# decoder.net
KiCad netlist of a schematic drawn in EAGLE
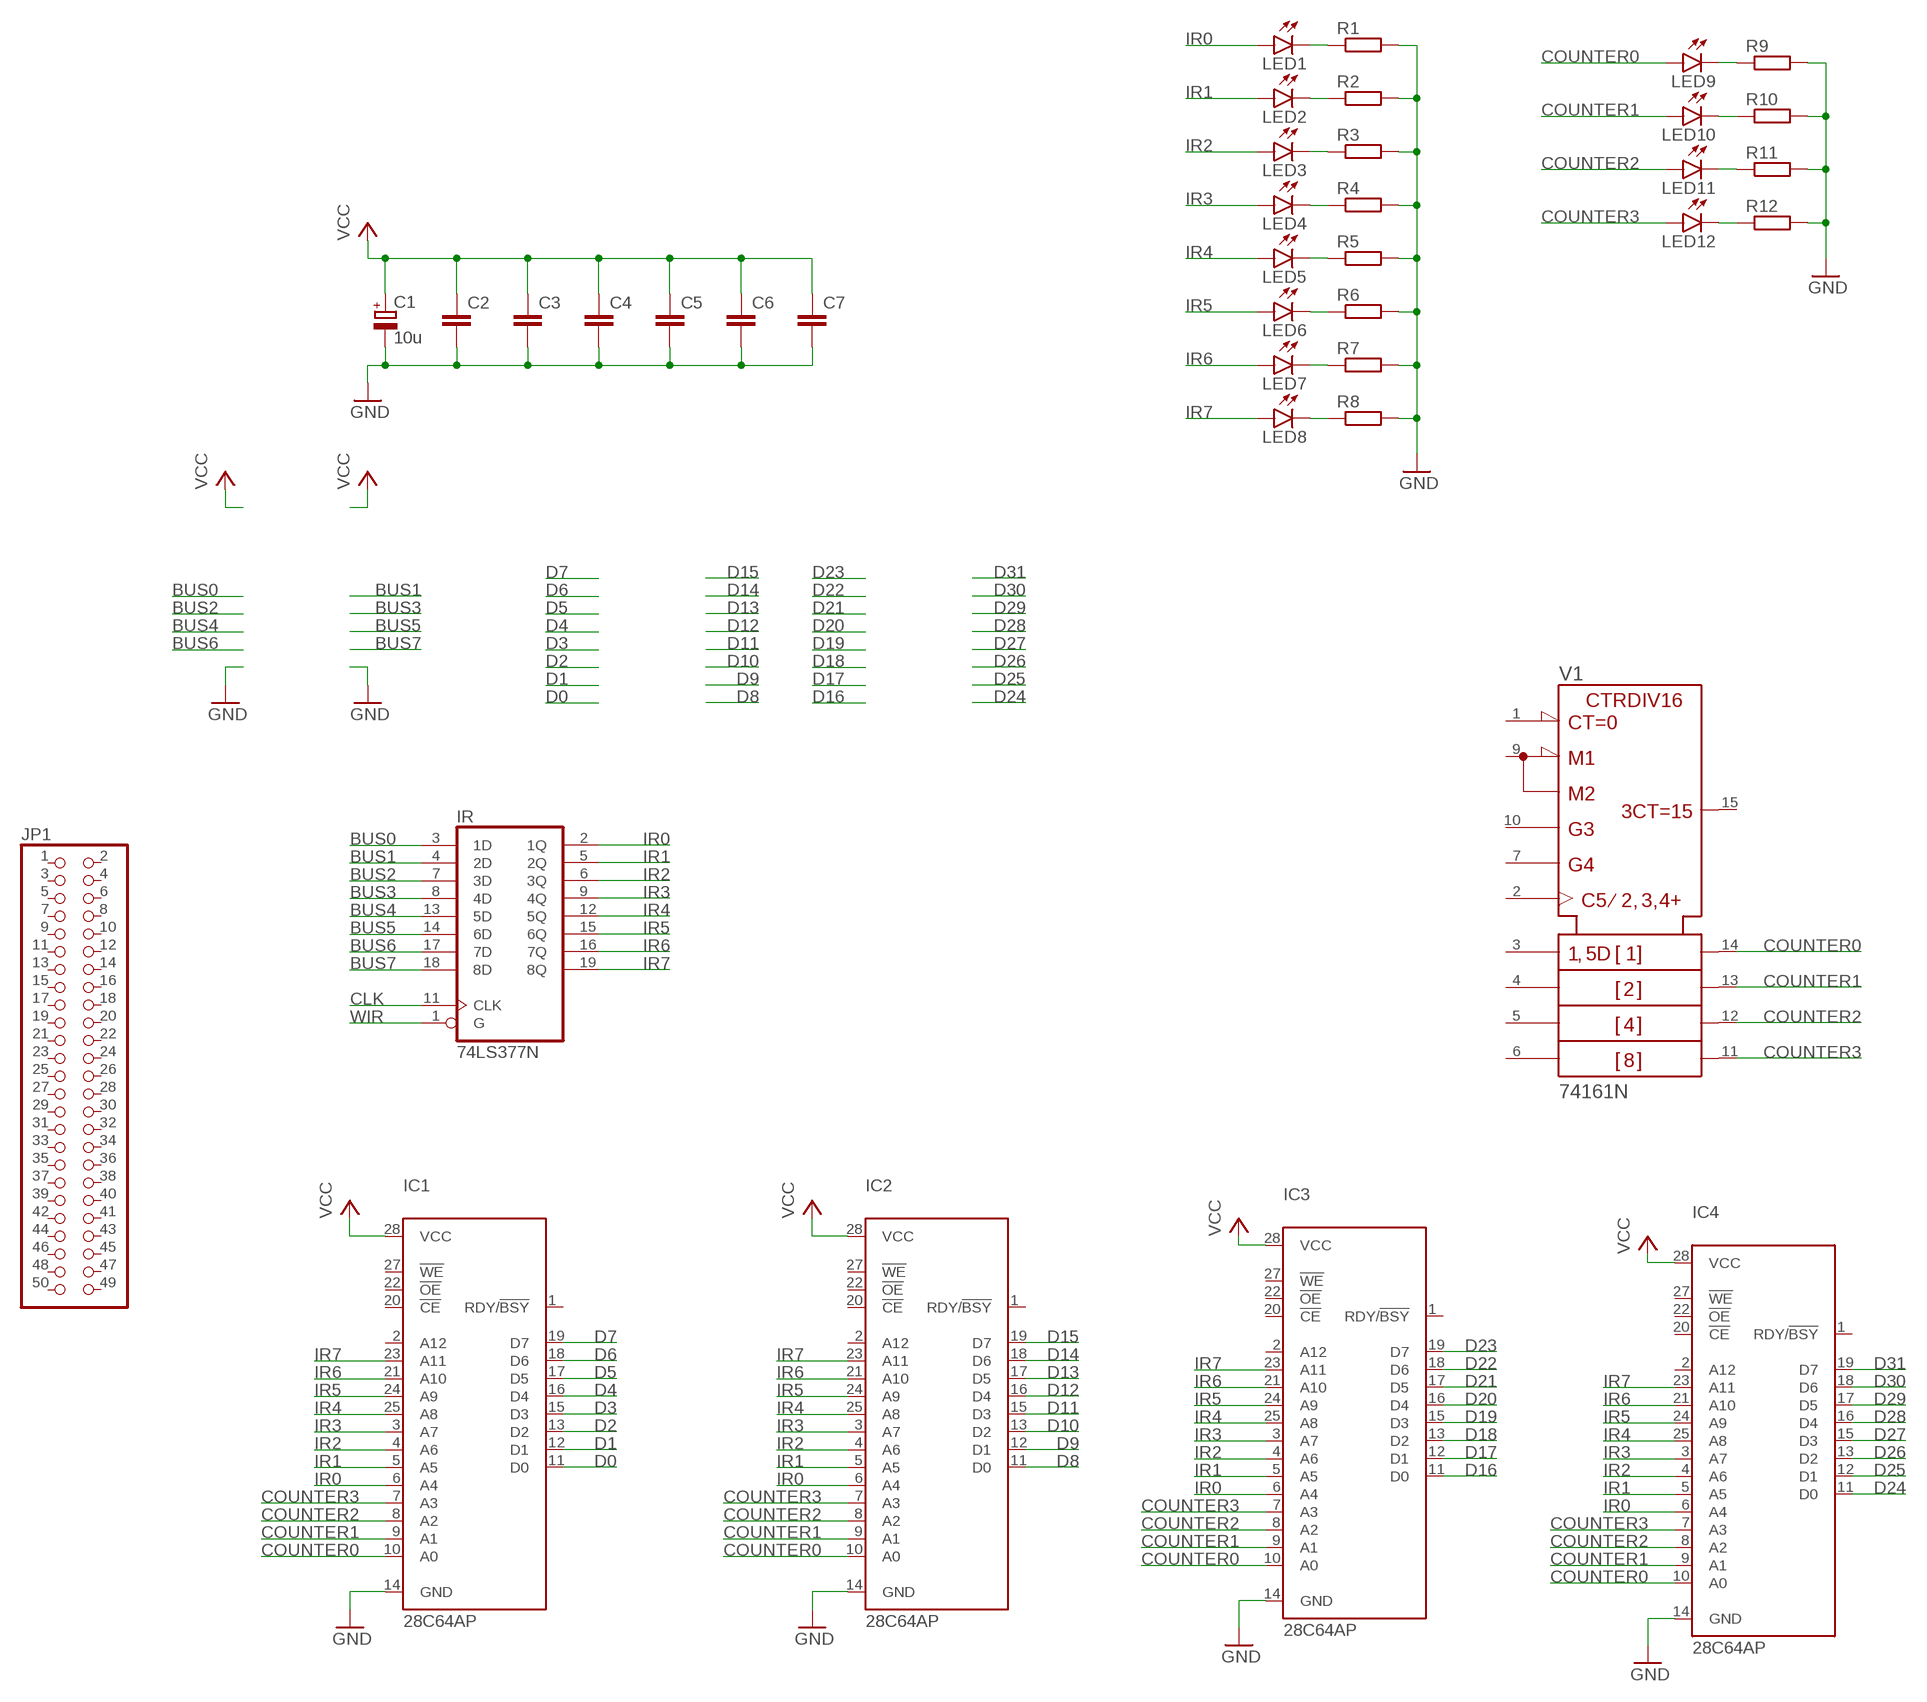
[diagram p0: schematic, sheet 1]

(export (version "E")
  (design (tool "Eeschema 10.0.6"))
  (components
    (comp (ref "C1")
      (value "10u")
      (footprint "eagle-import:E5-8,5")
      (libsource (lib "eagle-import") (part "CPOL-EUE5-8.5"))
    )
    (comp (ref "C2")
      (value "C-EU025-024X044")
      (footprint "eagle-import:C025-024X044")
      (libsource (lib "eagle-import") (part "C-EU025-024X044"))
    )
    (comp (ref "C3")
      (value "C-EU025-024X044")
      (footprint "eagle-import:C025-024X044")
      (libsource (lib "eagle-import") (part "C-EU025-024X044"))
    )
    (comp (ref "C4")
      (value "C-EU025-024X044")
      (footprint "eagle-import:C025-024X044")
      (libsource (lib "eagle-import") (part "C-EU025-024X044"))
    )
    (comp (ref "C5")
      (value "C-EU025-024X044")
      (footprint "eagle-import:C025-024X044")
      (libsource (lib "eagle-import") (part "C-EU025-024X044"))
    )
    (comp (ref "C6")
      (value "C-EU025-024X044")
      (footprint "eagle-import:C025-024X044")
      (libsource (lib "eagle-import") (part "C-EU025-024X044"))
    )
    (comp (ref "C7")
      (value "C-EU025-024X044")
      (footprint "eagle-import:C025-024X044")
      (libsource (lib "eagle-import") (part "C-EU025-024X044"))
    )
    (comp (ref "IC1")
      (value "28C64AP")
      (footprint "eagle-import:DIL28-6")
      (fields (field (name "MPN") "AT28C64B-15PU"))
      (libsource (lib "eagle-import") (part "2864APC"))
    )
    (comp (ref "IC2")
      (value "28C64AP")
      (footprint "eagle-import:DIL28-6")
      (fields (field (name "MPN") "AT28C64B-15PU"))
      (libsource (lib "eagle-import") (part "2864APC"))
    )
    (comp (ref "IC3")
      (value "28C64AP")
      (footprint "eagle-import:DIL28-6")
      (fields (field (name "MPN") "AT28C64B-15PU"))
      (libsource (lib "eagle-import") (part "2864APC"))
    )
    (comp (ref "IC4")
      (value "28C64AP")
      (footprint "eagle-import:DIL28-6")
      (fields (field (name "MPN") "AT28C64B-15PU"))
      (libsource (lib "eagle-import") (part "2864APC"))
    )
    (comp (ref "IR")
      (value "74LS377N")
      (footprint "eagle-import:DIL20")
      (libsource (lib "eagle-import") (part "74377NLS"))
    )
    (comp (ref "JP1")
      (value "PINHD-2X25/90")
      (footprint "eagle-import:2X25_90")
      (libsource (lib "eagle-import") (part "PINHD-2X25/90"))
    )
    (comp (ref "LED1")
      (value "LEDSML1206")
      (footprint "eagle-import:SML1206")
      (libsource (lib "eagle-import") (part "LEDSML1206"))
    )
    (comp (ref "LED2")
      (value "LEDSML1206")
      (footprint "eagle-import:SML1206")
      (libsource (lib "eagle-import") (part "LEDSML1206"))
    )
    (comp (ref "LED3")
      (value "LEDSML1206")
      (footprint "eagle-import:SML1206")
      (libsource (lib "eagle-import") (part "LEDSML1206"))
    )
    (comp (ref "LED4")
      (value "LEDSML1206")
      (footprint "eagle-import:SML1206")
      (libsource (lib "eagle-import") (part "LEDSML1206"))
    )
    (comp (ref "LED5")
      (value "LEDSML1206")
      (footprint "eagle-import:SML1206")
      (libsource (lib "eagle-import") (part "LEDSML1206"))
    )
    (comp (ref "LED6")
      (value "LEDSML1206")
      (footprint "eagle-import:SML1206")
      (libsource (lib "eagle-import") (part "LEDSML1206"))
    )
    (comp (ref "LED7")
      (value "LEDSML1206")
      (footprint "eagle-import:SML1206")
      (libsource (lib "eagle-import") (part "LEDSML1206"))
    )
    (comp (ref "LED8")
      (value "LEDSML1206")
      (footprint "eagle-import:SML1206")
      (libsource (lib "eagle-import") (part "LEDSML1206"))
    )
    (comp (ref "LED9")
      (value "LEDSML1206")
      (footprint "eagle-import:SML1206")
      (libsource (lib "eagle-import") (part "LEDSML1206"))
    )
    (comp (ref "LED10")
      (value "LEDSML1206")
      (footprint "eagle-import:SML1206")
      (libsource (lib "eagle-import") (part "LEDSML1206"))
    )
    (comp (ref "LED11")
      (value "LEDSML1206")
      (footprint "eagle-import:SML1206")
      (libsource (lib "eagle-import") (part "LEDSML1206"))
    )
    (comp (ref "LED12")
      (value "LEDSML1206")
      (footprint "eagle-import:SML1206")
      (libsource (lib "eagle-import") (part "LEDSML1206"))
    )
    (comp (ref "R1")
      (value "R-EU_R0805")
      (footprint "eagle-import:R0805")
      (libsource (lib "eagle-import") (part "R-EU_R0805"))
    )
    (comp (ref "R2")
      (value "R-EU_R0805")
      (footprint "eagle-import:R0805")
      (libsource (lib "eagle-import") (part "R-EU_R0805"))
    )
    (comp (ref "R3")
      (value "R-EU_R0805")
      (footprint "eagle-import:R0805")
      (libsource (lib "eagle-import") (part "R-EU_R0805"))
    )
    (comp (ref "R4")
      (value "R-EU_R0805")
      (footprint "eagle-import:R0805")
      (libsource (lib "eagle-import") (part "R-EU_R0805"))
    )
    (comp (ref "R5")
      (value "R-EU_R0805")
      (footprint "eagle-import:R0805")
      (libsource (lib "eagle-import") (part "R-EU_R0805"))
    )
    (comp (ref "R6")
      (value "R-EU_R0805")
      (footprint "eagle-import:R0805")
      (libsource (lib "eagle-import") (part "R-EU_R0805"))
    )
    (comp (ref "R7")
      (value "R-EU_R0805")
      (footprint "eagle-import:R0805")
      (libsource (lib "eagle-import") (part "R-EU_R0805"))
    )
    (comp (ref "R8")
      (value "R-EU_R0805")
      (footprint "eagle-import:R0805")
      (libsource (lib "eagle-import") (part "R-EU_R0805"))
    )
    (comp (ref "R9")
      (value "R-EU_R0805")
      (footprint "eagle-import:R0805")
      (libsource (lib "eagle-import") (part "R-EU_R0805"))
    )
    (comp (ref "R10")
      (value "R-EU_R0805")
      (footprint "eagle-import:R0805")
      (libsource (lib "eagle-import") (part "R-EU_R0805"))
    )
    (comp (ref "R11")
      (value "R-EU_R0805")
      (footprint "eagle-import:R0805")
      (libsource (lib "eagle-import") (part "R-EU_R0805"))
    )
    (comp (ref "R12")
      (value "R-EU_R0805")
      (footprint "eagle-import:R0805")
      (libsource (lib "eagle-import") (part "R-EU_R0805"))
    )
    (comp (ref "V1")
      (value "74161N")
      (footprint "eagle-import:DIL16")
      (libsource (lib "eagle-import") (part "74161N"))
    )
  )
  (nets
    (net (code "1") (name "/BUS0") (class "Default")
      (node (ref "IR") (pin "3") (pinfunction "1D_3") (pintype "input"))
    )
    (net (code "2") (name "/BUS1") (class "Default")
      (node (ref "IR") (pin "4") (pinfunction "2D_4") (pintype "input"))
    )
    (net (code "3") (name "/BUS2") (class "Default")
      (node (ref "IR") (pin "7") (pinfunction "3D_7") (pintype "input"))
    )
    (net (code "4") (name "/BUS3") (class "Default")
      (node (ref "IR") (pin "8") (pinfunction "4D_8") (pintype "input"))
    )
    (net (code "5") (name "/BUS4") (class "Default")
      (node (ref "IR") (pin "13") (pinfunction "5D_13") (pintype "input"))
    )
    (net (code "6") (name "/BUS5") (class "Default")
      (node (ref "IR") (pin "14") (pinfunction "6D_14") (pintype "input"))
    )
    (net (code "7") (name "/BUS6") (class "Default")
      (node (ref "IR") (pin "17") (pinfunction "7D_17") (pintype "input"))
    )
    (net (code "8") (name "/BUS7") (class "Default")
      (node (ref "IR") (pin "18") (pinfunction "8D_18") (pintype "input"))
    )
    (net (code "9") (name "/CLK") (class "Default")
      (node (ref "IR") (pin "11") (pinfunction "CLK_11") (pintype "input"))
    )
    (net (code "10") (name "/COUNTER0") (class "Default")
      (node (ref "IC1") (pin "10") (pinfunction "A0_10") (pintype "input"))
      (node (ref "IC2") (pin "10") (pinfunction "A0_10") (pintype "input"))
      (node (ref "IC3") (pin "10") (pinfunction "A0_10") (pintype "input"))
      (node (ref "IC4") (pin "10") (pinfunction "A0_10") (pintype "input"))
      (node (ref "LED9") (pin "A") (pinfunction "A_A") (pintype "passive"))
      (node (ref "V1") (pin "14") (pinfunction "QA_14") (pintype "output"))
    )
    (net (code "11") (name "/COUNTER1") (class "Default")
      (node (ref "IC1") (pin "9") (pinfunction "A1_9") (pintype "input"))
      (node (ref "IC2") (pin "9") (pinfunction "A1_9") (pintype "input"))
      (node (ref "IC3") (pin "9") (pinfunction "A1_9") (pintype "input"))
      (node (ref "IC4") (pin "9") (pinfunction "A1_9") (pintype "input"))
      (node (ref "LED10") (pin "A") (pinfunction "A_A") (pintype "passive"))
      (node (ref "V1") (pin "13") (pinfunction "QB_13") (pintype "output"))
    )
    (net (code "12") (name "/COUNTER2") (class "Default")
      (node (ref "IC1") (pin "8") (pinfunction "A2_8") (pintype "input"))
      (node (ref "IC2") (pin "8") (pinfunction "A2_8") (pintype "input"))
      (node (ref "IC3") (pin "8") (pinfunction "A2_8") (pintype "input"))
      (node (ref "IC4") (pin "8") (pinfunction "A2_8") (pintype "input"))
      (node (ref "LED11") (pin "A") (pinfunction "A_A") (pintype "passive"))
      (node (ref "V1") (pin "12") (pinfunction "QC_12") (pintype "output"))
    )
    (net (code "13") (name "/COUNTER3") (class "Default")
      (node (ref "IC1") (pin "7") (pinfunction "A3_7") (pintype "input"))
      (node (ref "IC2") (pin "7") (pinfunction "A3_7") (pintype "input"))
      (node (ref "IC3") (pin "7") (pinfunction "A3_7") (pintype "input"))
      (node (ref "IC4") (pin "7") (pinfunction "A3_7") (pintype "input"))
      (node (ref "LED12") (pin "A") (pinfunction "A_A") (pintype "passive"))
      (node (ref "V1") (pin "11") (pinfunction "QD_11") (pintype "output"))
    )
    (net (code "14") (name "/D0") (class "Default")
      (node (ref "IC1") (pin "11") (pinfunction "D0_11") (pintype "tri_state"))
    )
    (net (code "15") (name "/D1") (class "Default")
      (node (ref "IC1") (pin "12") (pinfunction "D1_12") (pintype "tri_state"))
    )
    (net (code "16") (name "/D2") (class "Default")
      (node (ref "IC1") (pin "13") (pinfunction "D2_13") (pintype "tri_state"))
    )
    (net (code "17") (name "/D3") (class "Default")
      (node (ref "IC1") (pin "15") (pinfunction "D3_15") (pintype "tri_state"))
    )
    (net (code "18") (name "/D4") (class "Default")
      (node (ref "IC1") (pin "16") (pinfunction "D4_16") (pintype "tri_state"))
    )
    (net (code "19") (name "/D5") (class "Default")
      (node (ref "IC1") (pin "17") (pinfunction "D5_17") (pintype "tri_state"))
    )
    (net (code "20") (name "/D6") (class "Default")
      (node (ref "IC1") (pin "18") (pinfunction "D6_18") (pintype "tri_state"))
    )
    (net (code "21") (name "/D7") (class "Default")
      (node (ref "IC1") (pin "19") (pinfunction "D7_19") (pintype "tri_state"))
    )
    (net (code "22") (name "/D8") (class "Default")
      (node (ref "IC2") (pin "11") (pinfunction "D0_11") (pintype "tri_state"))
    )
    (net (code "23") (name "/D9") (class "Default")
      (node (ref "IC2") (pin "12") (pinfunction "D1_12") (pintype "tri_state"))
    )
    (net (code "24") (name "/D10") (class "Default")
      (node (ref "IC2") (pin "13") (pinfunction "D2_13") (pintype "tri_state"))
    )
    (net (code "25") (name "/D11") (class "Default")
      (node (ref "IC2") (pin "15") (pinfunction "D3_15") (pintype "tri_state"))
    )
    (net (code "26") (name "/D12") (class "Default")
      (node (ref "IC2") (pin "16") (pinfunction "D4_16") (pintype "tri_state"))
    )
    (net (code "27") (name "/D13") (class "Default")
      (node (ref "IC2") (pin "17") (pinfunction "D5_17") (pintype "tri_state"))
    )
    (net (code "28") (name "/D14") (class "Default")
      (node (ref "IC2") (pin "18") (pinfunction "D6_18") (pintype "tri_state"))
    )
    (net (code "29") (name "/D15") (class "Default")
      (node (ref "IC2") (pin "19") (pinfunction "D7_19") (pintype "tri_state"))
    )
    (net (code "30") (name "/D16") (class "Default")
      (node (ref "IC3") (pin "11") (pinfunction "D0_11") (pintype "tri_state"))
    )
    (net (code "31") (name "/D17") (class "Default")
      (node (ref "IC3") (pin "12") (pinfunction "D1_12") (pintype "tri_state"))
    )
    (net (code "32") (name "/D18") (class "Default")
      (node (ref "IC3") (pin "13") (pinfunction "D2_13") (pintype "tri_state"))
    )
    (net (code "33") (name "/D19") (class "Default")
      (node (ref "IC3") (pin "15") (pinfunction "D3_15") (pintype "tri_state"))
    )
    (net (code "34") (name "/D20") (class "Default")
      (node (ref "IC3") (pin "16") (pinfunction "D4_16") (pintype "tri_state"))
    )
    (net (code "35") (name "/D21") (class "Default")
      (node (ref "IC3") (pin "17") (pinfunction "D5_17") (pintype "tri_state"))
    )
    (net (code "36") (name "/D22") (class "Default")
      (node (ref "IC3") (pin "18") (pinfunction "D6_18") (pintype "tri_state"))
    )
    (net (code "37") (name "/D23") (class "Default")
      (node (ref "IC3") (pin "19") (pinfunction "D7_19") (pintype "tri_state"))
    )
    (net (code "38") (name "/D24") (class "Default")
      (node (ref "IC4") (pin "11") (pinfunction "D0_11") (pintype "tri_state"))
    )
    (net (code "39") (name "/D25") (class "Default")
      (node (ref "IC4") (pin "12") (pinfunction "D1_12") (pintype "tri_state"))
    )
    (net (code "40") (name "/D26") (class "Default")
      (node (ref "IC4") (pin "13") (pinfunction "D2_13") (pintype "tri_state"))
    )
    (net (code "41") (name "/D27") (class "Default")
      (node (ref "IC4") (pin "15") (pinfunction "D3_15") (pintype "tri_state"))
    )
    (net (code "42") (name "/D28") (class "Default")
      (node (ref "IC4") (pin "16") (pinfunction "D4_16") (pintype "tri_state"))
    )
    (net (code "43") (name "/D29") (class "Default")
      (node (ref "IC4") (pin "17") (pinfunction "D5_17") (pintype "tri_state"))
    )
    (net (code "44") (name "/D30") (class "Default")
      (node (ref "IC4") (pin "18") (pinfunction "D6_18") (pintype "tri_state"))
    )
    (net (code "45") (name "/D31") (class "Default")
      (node (ref "IC4") (pin "19") (pinfunction "D7_19") (pintype "tri_state"))
    )
    (net (code "46") (name "/IR0") (class "Default")
      (node (ref "IC1") (pin "6") (pinfunction "A4_6") (pintype "input"))
      (node (ref "IC2") (pin "6") (pinfunction "A4_6") (pintype "input"))
      (node (ref "IC3") (pin "6") (pinfunction "A4_6") (pintype "input"))
      (node (ref "IC4") (pin "6") (pinfunction "A4_6") (pintype "input"))
      (node (ref "IR") (pin "2") (pinfunction "1Q_2") (pintype "output"))
      (node (ref "LED1") (pin "A") (pinfunction "A_A") (pintype "passive"))
    )
    (net (code "47") (name "/IR1") (class "Default")
      (node (ref "IC1") (pin "5") (pinfunction "A5_5") (pintype "input"))
      (node (ref "IC2") (pin "5") (pinfunction "A5_5") (pintype "input"))
      (node (ref "IC3") (pin "5") (pinfunction "A5_5") (pintype "input"))
      (node (ref "IC4") (pin "5") (pinfunction "A5_5") (pintype "input"))
      (node (ref "IR") (pin "5") (pinfunction "2Q_5") (pintype "output"))
      (node (ref "LED2") (pin "A") (pinfunction "A_A") (pintype "passive"))
    )
    (net (code "48") (name "/IR2") (class "Default")
      (node (ref "IC1") (pin "4") (pinfunction "A6_4") (pintype "input"))
      (node (ref "IC2") (pin "4") (pinfunction "A6_4") (pintype "input"))
      (node (ref "IC3") (pin "4") (pinfunction "A6_4") (pintype "input"))
      (node (ref "IC4") (pin "4") (pinfunction "A6_4") (pintype "input"))
      (node (ref "IR") (pin "6") (pinfunction "3Q_6") (pintype "output"))
      (node (ref "LED3") (pin "A") (pinfunction "A_A") (pintype "passive"))
    )
    (net (code "49") (name "/IR3") (class "Default")
      (node (ref "IC1") (pin "3") (pinfunction "A7_3") (pintype "input"))
      (node (ref "IC2") (pin "3") (pinfunction "A7_3") (pintype "input"))
      (node (ref "IC3") (pin "3") (pinfunction "A7_3") (pintype "input"))
      (node (ref "IC4") (pin "3") (pinfunction "A7_3") (pintype "input"))
      (node (ref "IR") (pin "9") (pinfunction "4Q_9") (pintype "output"))
      (node (ref "LED4") (pin "A") (pinfunction "A_A") (pintype "passive"))
    )
    (net (code "50") (name "/IR4") (class "Default")
      (node (ref "IC1") (pin "25") (pinfunction "A8_25") (pintype "input"))
      (node (ref "IC2") (pin "25") (pinfunction "A8_25") (pintype "input"))
      (node (ref "IC3") (pin "25") (pinfunction "A8_25") (pintype "input"))
      (node (ref "IC4") (pin "25") (pinfunction "A8_25") (pintype "input"))
      (node (ref "IR") (pin "12") (pinfunction "5Q_12") (pintype "output"))
      (node (ref "LED5") (pin "A") (pinfunction "A_A") (pintype "passive"))
    )
    (net (code "51") (name "/IR5") (class "Default")
      (node (ref "IC1") (pin "24") (pinfunction "A9_24") (pintype "input"))
      (node (ref "IC2") (pin "24") (pinfunction "A9_24") (pintype "input"))
      (node (ref "IC3") (pin "24") (pinfunction "A9_24") (pintype "input"))
      (node (ref "IC4") (pin "24") (pinfunction "A9_24") (pintype "input"))
      (node (ref "IR") (pin "15") (pinfunction "6Q_15") (pintype "output"))
      (node (ref "LED6") (pin "A") (pinfunction "A_A") (pintype "passive"))
    )
    (net (code "52") (name "/IR6") (class "Default")
      (node (ref "IC1") (pin "21") (pinfunction "A10_21") (pintype "input"))
      (node (ref "IC2") (pin "21") (pinfunction "A10_21") (pintype "input"))
      (node (ref "IC3") (pin "21") (pinfunction "A10_21") (pintype "input"))
      (node (ref "IC4") (pin "21") (pinfunction "A10_21") (pintype "input"))
      (node (ref "IR") (pin "16") (pinfunction "7Q_16") (pintype "output"))
      (node (ref "LED7") (pin "A") (pinfunction "A_A") (pintype "passive"))
    )
    (net (code "53") (name "/IR7") (class "Default")
      (node (ref "IC1") (pin "23") (pinfunction "A11_23") (pintype "input"))
      (node (ref "IC2") (pin "23") (pinfunction "A11_23") (pintype "input"))
      (node (ref "IC3") (pin "23") (pinfunction "A11_23") (pintype "input"))
      (node (ref "IC4") (pin "23") (pinfunction "A11_23") (pintype "input"))
      (node (ref "IR") (pin "19") (pinfunction "8Q_19") (pintype "output"))
      (node (ref "LED8") (pin "A") (pinfunction "A_A") (pintype "passive"))
    )
    (net (code "54") (name "/WIR") (class "Default")
      (node (ref "IR") (pin "1") (pinfunction "G_1") (pintype "input"))
    )
    (net (code "55") (name "GND") (class "Default")
      (node (ref "C1") (pin "-") (pinfunction "-_-") (pintype "passive"))
      (node (ref "C2") (pin "2") (pinfunction "2_2") (pintype "passive"))
      (node (ref "C3") (pin "2") (pinfunction "2_2") (pintype "passive"))
      (node (ref "C4") (pin "2") (pinfunction "2_2") (pintype "passive"))
      (node (ref "C5") (pin "2") (pinfunction "2_2") (pintype "passive"))
      (node (ref "C6") (pin "2") (pinfunction "2_2") (pintype "passive"))
      (node (ref "C7") (pin "2") (pinfunction "2_2") (pintype "passive"))
      (node (ref "IC1") (pin "14") (pinfunction "GND_14") (pintype "power_in"))
      (node (ref "IC2") (pin "14") (pinfunction "GND_14") (pintype "power_in"))
      (node (ref "IC3") (pin "14") (pinfunction "GND_14") (pintype "power_in"))
      (node (ref "IC4") (pin "14") (pinfunction "GND_14") (pintype "power_in"))
      (node (ref "R1") (pin "2") (pinfunction "2_2") (pintype "passive"))
      (node (ref "R10") (pin "2") (pinfunction "2_2") (pintype "passive"))
      (node (ref "R11") (pin "2") (pinfunction "2_2") (pintype "passive"))
      (node (ref "R12") (pin "2") (pinfunction "2_2") (pintype "passive"))
      (node (ref "R2") (pin "2") (pinfunction "2_2") (pintype "passive"))
      (node (ref "R3") (pin "2") (pinfunction "2_2") (pintype "passive"))
      (node (ref "R4") (pin "2") (pinfunction "2_2") (pintype "passive"))
      (node (ref "R5") (pin "2") (pinfunction "2_2") (pintype "passive"))
      (node (ref "R6") (pin "2") (pinfunction "2_2") (pintype "passive"))
      (node (ref "R7") (pin "2") (pinfunction "2_2") (pintype "passive"))
      (node (ref "R8") (pin "2") (pinfunction "2_2") (pintype "passive"))
      (node (ref "R9") (pin "2") (pinfunction "2_2") (pintype "passive"))
    )
    (net (code "56") (name "Net-(LED1-PadC)") (class "Default")
      (node (ref "LED1") (pin "C") (pinfunction "C_C") (pintype "passive"))
      (node (ref "R1") (pin "1") (pinfunction "1_1") (pintype "passive"))
    )
    (net (code "57") (name "Net-(LED2-PadC)") (class "Default")
      (node (ref "LED2") (pin "C") (pinfunction "C_C") (pintype "passive"))
      (node (ref "R2") (pin "1") (pinfunction "1_1") (pintype "passive"))
    )
    (net (code "58") (name "Net-(LED3-PadC)") (class "Default")
      (node (ref "LED3") (pin "C") (pinfunction "C_C") (pintype "passive"))
      (node (ref "R3") (pin "1") (pinfunction "1_1") (pintype "passive"))
    )
    (net (code "59") (name "Net-(LED4-PadC)") (class "Default")
      (node (ref "LED4") (pin "C") (pinfunction "C_C") (pintype "passive"))
      (node (ref "R4") (pin "1") (pinfunction "1_1") (pintype "passive"))
    )
    (net (code "60") (name "Net-(LED5-PadC)") (class "Default")
      (node (ref "LED5") (pin "C") (pinfunction "C_C") (pintype "passive"))
      (node (ref "R5") (pin "1") (pinfunction "1_1") (pintype "passive"))
    )
    (net (code "61") (name "Net-(LED6-PadC)") (class "Default")
      (node (ref "LED6") (pin "C") (pinfunction "C_C") (pintype "passive"))
      (node (ref "R6") (pin "1") (pinfunction "1_1") (pintype "passive"))
    )
    (net (code "62") (name "Net-(LED7-PadC)") (class "Default")
      (node (ref "LED7") (pin "C") (pinfunction "C_C") (pintype "passive"))
      (node (ref "R7") (pin "1") (pinfunction "1_1") (pintype "passive"))
    )
    (net (code "63") (name "Net-(LED8-PadC)") (class "Default")
      (node (ref "LED8") (pin "C") (pinfunction "C_C") (pintype "passive"))
      (node (ref "R8") (pin "1") (pinfunction "1_1") (pintype "passive"))
    )
    (net (code "64") (name "Net-(LED9-PadC)") (class "Default")
      (node (ref "LED9") (pin "C") (pinfunction "C_C") (pintype "passive"))
      (node (ref "R9") (pin "1") (pinfunction "1_1") (pintype "passive"))
    )
    (net (code "65") (name "Net-(LED10-PadC)") (class "Default")
      (node (ref "LED10") (pin "C") (pinfunction "C_C") (pintype "passive"))
      (node (ref "R10") (pin "1") (pinfunction "1_1") (pintype "passive"))
    )
    (net (code "66") (name "Net-(LED11-PadC)") (class "Default")
      (node (ref "LED11") (pin "C") (pinfunction "C_C") (pintype "passive"))
      (node (ref "R11") (pin "1") (pinfunction "1_1") (pintype "passive"))
    )
    (net (code "67") (name "Net-(LED12-PadC)") (class "Default")
      (node (ref "LED12") (pin "C") (pinfunction "C_C") (pintype "passive"))
      (node (ref "R12") (pin "1") (pinfunction "1_1") (pintype "passive"))
    )
    (net (code "68") (name "VCC") (class "Default")
      (node (ref "C1") (pin "+") (pinfunction "+_+") (pintype "passive"))
      (node (ref "C2") (pin "1") (pinfunction "1_1") (pintype "passive"))
      (node (ref "C3") (pin "1") (pinfunction "1_1") (pintype "passive"))
      (node (ref "C4") (pin "1") (pinfunction "1_1") (pintype "passive"))
      (node (ref "C5") (pin "1") (pinfunction "1_1") (pintype "passive"))
      (node (ref "C6") (pin "1") (pinfunction "1_1") (pintype "passive"))
      (node (ref "C7") (pin "1") (pinfunction "1_1") (pintype "passive"))
      (node (ref "IC1") (pin "28") (pinfunction "VCC_28") (pintype "power_in"))
      (node (ref "IC2") (pin "28") (pinfunction "VCC_28") (pintype "power_in"))
      (node (ref "IC3") (pin "28") (pinfunction "VCC_28") (pintype "power_in"))
      (node (ref "IC4") (pin "28") (pinfunction "VCC_28") (pintype "power_in"))
    )
    (net (code "69") (name "unconnected-(IC1-A12-Pad2)") (class "Default")
      (node (ref "IC1") (pin "2") (pinfunction "A12_2") (pintype "input"))
    )
    (net (code "70") (name "unconnected-(IC1-RDY{slash}~{BSY}-Pad1)") (class "Default")
      (node (ref "IC1") (pin "1") (pinfunction "RDY/~{BSY}_1") (pintype "output"))
    )
    (net (code "71") (name "unconnected-(IC1-~{CE}-Pad20)") (class "Default")
      (node (ref "IC1") (pin "20") (pinfunction "~{CE}_20") (pintype "input"))
    )
    (net (code "72") (name "unconnected-(IC1-~{OE}-Pad22)") (class "Default")
      (node (ref "IC1") (pin "22") (pinfunction "~{OE}_22") (pintype "input"))
    )
    (net (code "73") (name "unconnected-(IC1-~{WE}-Pad27)") (class "Default")
      (node (ref "IC1") (pin "27") (pinfunction "~{WE}_27") (pintype "input"))
    )
    (net (code "74") (name "unconnected-(IC2-A12-Pad2)") (class "Default")
      (node (ref "IC2") (pin "2") (pinfunction "A12_2") (pintype "input"))
    )
    (net (code "75") (name "unconnected-(IC2-RDY{slash}~{BSY}-Pad1)") (class "Default")
      (node (ref "IC2") (pin "1") (pinfunction "RDY/~{BSY}_1") (pintype "output"))
    )
    (net (code "76") (name "unconnected-(IC2-~{CE}-Pad20)") (class "Default")
      (node (ref "IC2") (pin "20") (pinfunction "~{CE}_20") (pintype "input"))
    )
    (net (code "77") (name "unconnected-(IC2-~{OE}-Pad22)") (class "Default")
      (node (ref "IC2") (pin "22") (pinfunction "~{OE}_22") (pintype "input"))
    )
    (net (code "78") (name "unconnected-(IC2-~{WE}-Pad27)") (class "Default")
      (node (ref "IC2") (pin "27") (pinfunction "~{WE}_27") (pintype "input"))
    )
    (net (code "79") (name "unconnected-(IC3-A12-Pad2)") (class "Default")
      (node (ref "IC3") (pin "2") (pinfunction "A12_2") (pintype "input"))
    )
    (net (code "80") (name "unconnected-(IC3-RDY{slash}~{BSY}-Pad1)") (class "Default")
      (node (ref "IC3") (pin "1") (pinfunction "RDY/~{BSY}_1") (pintype "output"))
    )
    (net (code "81") (name "unconnected-(IC3-~{CE}-Pad20)") (class "Default")
      (node (ref "IC3") (pin "20") (pinfunction "~{CE}_20") (pintype "input"))
    )
    (net (code "82") (name "unconnected-(IC3-~{OE}-Pad22)") (class "Default")
      (node (ref "IC3") (pin "22") (pinfunction "~{OE}_22") (pintype "input"))
    )
    (net (code "83") (name "unconnected-(IC3-~{WE}-Pad27)") (class "Default")
      (node (ref "IC3") (pin "27") (pinfunction "~{WE}_27") (pintype "input"))
    )
    (net (code "84") (name "unconnected-(IC4-A12-Pad2)") (class "Default")
      (node (ref "IC4") (pin "2") (pinfunction "A12_2") (pintype "input"))
    )
    (net (code "85") (name "unconnected-(IC4-RDY{slash}~{BSY}-Pad1)") (class "Default")
      (node (ref "IC4") (pin "1") (pinfunction "RDY/~{BSY}_1") (pintype "output"))
    )
    (net (code "86") (name "unconnected-(IC4-~{CE}-Pad20)") (class "Default")
      (node (ref "IC4") (pin "20") (pinfunction "~{CE}_20") (pintype "input"))
    )
    (net (code "87") (name "unconnected-(IC4-~{OE}-Pad22)") (class "Default")
      (node (ref "IC4") (pin "22") (pinfunction "~{OE}_22") (pintype "input"))
    )
    (net (code "88") (name "unconnected-(IC4-~{WE}-Pad27)") (class "Default")
      (node (ref "IC4") (pin "27") (pinfunction "~{WE}_27") (pintype "input"))
    )
    (net (code "89") (name "unconnected-(JP1-41-Pad42)") (class "Default")
      (node (ref "JP1") (pin "42") (pinfunction "41_42") (pintype "passive"))
    )
    (net (code "90") (name "unconnected-(JP1-42-Pad41)") (class "Default")
      (node (ref "JP1") (pin "41") (pinfunction "42_41") (pintype "passive"))
    )
    (net (code "91") (name "unconnected-(JP1-43-Pad44)") (class "Default")
      (node (ref "JP1") (pin "44") (pinfunction "43_44") (pintype "passive"))
    )
    (net (code "92") (name "unconnected-(JP1-44-Pad43)") (class "Default")
      (node (ref "JP1") (pin "43") (pinfunction "44_43") (pintype "passive"))
    )
    (net (code "93") (name "unconnected-(JP1-45-Pad46)") (class "Default")
      (node (ref "JP1") (pin "46") (pinfunction "45_46") (pintype "passive"))
    )
    (net (code "94") (name "unconnected-(JP1-46-Pad45)") (class "Default")
      (node (ref "JP1") (pin "45") (pinfunction "46_45") (pintype "passive"))
    )
    (net (code "95") (name "unconnected-(JP1-47-Pad48)") (class "Default")
      (node (ref "JP1") (pin "48") (pinfunction "47_48") (pintype "passive"))
    )
    (net (code "96") (name "unconnected-(JP1-48-Pad47)") (class "Default")
      (node (ref "JP1") (pin "47") (pinfunction "48_47") (pintype "passive"))
    )
    (net (code "97") (name "unconnected-(JP1-49-Pad50)") (class "Default")
      (node (ref "JP1") (pin "50") (pinfunction "49_50") (pintype "passive"))
    )
    (net (code "98") (name "unconnected-(JP1-50-Pad49)") (class "Default")
      (node (ref "JP1") (pin "49") (pinfunction "50_49") (pintype "passive"))
    )
    (net (code "99") (name "unconnected-(JP1-Pad1)") (class "Default")
      (node (ref "JP1") (pin "1") (pinfunction "1_1") (pintype "passive"))
    )
    (net (code "100") (name "unconnected-(JP1-Pad2)") (class "Default")
      (node (ref "JP1") (pin "2") (pinfunction "2_2") (pintype "passive"))
    )
    (net (code "101") (name "unconnected-(JP1-Pad3)") (class "Default")
      (node (ref "JP1") (pin "3") (pinfunction "3_3") (pintype "passive"))
    )
    (net (code "102") (name "unconnected-(JP1-Pad4)") (class "Default")
      (node (ref "JP1") (pin "4") (pinfunction "4_4") (pintype "passive"))
    )
    (net (code "103") (name "unconnected-(JP1-Pad5)") (class "Default")
      (node (ref "JP1") (pin "5") (pinfunction "5_5") (pintype "passive"))
    )
    (net (code "104") (name "unconnected-(JP1-Pad6)") (class "Default")
      (node (ref "JP1") (pin "6") (pinfunction "6_6") (pintype "passive"))
    )
    (net (code "105") (name "unconnected-(JP1-Pad7)") (class "Default")
      (node (ref "JP1") (pin "7") (pinfunction "7_7") (pintype "passive"))
    )
    (net (code "106") (name "unconnected-(JP1-Pad8)") (class "Default")
      (node (ref "JP1") (pin "8") (pinfunction "8_8") (pintype "passive"))
    )
    (net (code "107") (name "unconnected-(JP1-Pad9)") (class "Default")
      (node (ref "JP1") (pin "9") (pinfunction "9_9") (pintype "passive"))
    )
    (net (code "108") (name "unconnected-(JP1-Pad10)") (class "Default")
      (node (ref "JP1") (pin "10") (pinfunction "10_10") (pintype "passive"))
    )
    (net (code "109") (name "unconnected-(JP1-Pad11)") (class "Default")
      (node (ref "JP1") (pin "11") (pinfunction "11_11") (pintype "passive"))
    )
    (net (code "110") (name "unconnected-(JP1-Pad12)") (class "Default")
      (node (ref "JP1") (pin "12") (pinfunction "12_12") (pintype "passive"))
    )
    (net (code "111") (name "unconnected-(JP1-Pad13)") (class "Default")
      (node (ref "JP1") (pin "13") (pinfunction "13_13") (pintype "passive"))
    )
    (net (code "112") (name "unconnected-(JP1-Pad14)") (class "Default")
      (node (ref "JP1") (pin "14") (pinfunction "14_14") (pintype "passive"))
    )
    (net (code "113") (name "unconnected-(JP1-Pad15)") (class "Default")
      (node (ref "JP1") (pin "15") (pinfunction "15_15") (pintype "passive"))
    )
    (net (code "114") (name "unconnected-(JP1-Pad16)") (class "Default")
      (node (ref "JP1") (pin "16") (pinfunction "16_16") (pintype "passive"))
    )
    (net (code "115") (name "unconnected-(JP1-Pad17)") (class "Default")
      (node (ref "JP1") (pin "17") (pinfunction "17_17") (pintype "passive"))
    )
    (net (code "116") (name "unconnected-(JP1-Pad18)") (class "Default")
      (node (ref "JP1") (pin "18") (pinfunction "18_18") (pintype "passive"))
    )
    (net (code "117") (name "unconnected-(JP1-Pad19)") (class "Default")
      (node (ref "JP1") (pin "19") (pinfunction "19_19") (pintype "passive"))
    )
    (net (code "118") (name "unconnected-(JP1-Pad20)") (class "Default")
      (node (ref "JP1") (pin "20") (pinfunction "20_20") (pintype "passive"))
    )
    (net (code "119") (name "unconnected-(JP1-Pad21)") (class "Default")
      (node (ref "JP1") (pin "21") (pinfunction "21_21") (pintype "passive"))
    )
    (net (code "120") (name "unconnected-(JP1-Pad22)") (class "Default")
      (node (ref "JP1") (pin "22") (pinfunction "22_22") (pintype "passive"))
    )
    (net (code "121") (name "unconnected-(JP1-Pad23)") (class "Default")
      (node (ref "JP1") (pin "23") (pinfunction "23_23") (pintype "passive"))
    )
    (net (code "122") (name "unconnected-(JP1-Pad24)") (class "Default")
      (node (ref "JP1") (pin "24") (pinfunction "24_24") (pintype "passive"))
    )
    (net (code "123") (name "unconnected-(JP1-Pad25)") (class "Default")
      (node (ref "JP1") (pin "25") (pinfunction "25_25") (pintype "passive"))
    )
    (net (code "124") (name "unconnected-(JP1-Pad26)") (class "Default")
      (node (ref "JP1") (pin "26") (pinfunction "26_26") (pintype "passive"))
    )
    (net (code "125") (name "unconnected-(JP1-Pad27)") (class "Default")
      (node (ref "JP1") (pin "27") (pinfunction "27_27") (pintype "passive"))
    )
    (net (code "126") (name "unconnected-(JP1-Pad28)") (class "Default")
      (node (ref "JP1") (pin "28") (pinfunction "28_28") (pintype "passive"))
    )
    (net (code "127") (name "unconnected-(JP1-Pad29)") (class "Default")
      (node (ref "JP1") (pin "29") (pinfunction "29_29") (pintype "passive"))
    )
    (net (code "128") (name "unconnected-(JP1-Pad30)") (class "Default")
      (node (ref "JP1") (pin "30") (pinfunction "30_30") (pintype "passive"))
    )
    (net (code "129") (name "unconnected-(JP1-Pad31)") (class "Default")
      (node (ref "JP1") (pin "31") (pinfunction "31_31") (pintype "passive"))
    )
    (net (code "130") (name "unconnected-(JP1-Pad32)") (class "Default")
      (node (ref "JP1") (pin "32") (pinfunction "32_32") (pintype "passive"))
    )
    (net (code "131") (name "unconnected-(JP1-Pad33)") (class "Default")
      (node (ref "JP1") (pin "33") (pinfunction "33_33") (pintype "passive"))
    )
    (net (code "132") (name "unconnected-(JP1-Pad34)") (class "Default")
      (node (ref "JP1") (pin "34") (pinfunction "34_34") (pintype "passive"))
    )
    (net (code "133") (name "unconnected-(JP1-Pad35)") (class "Default")
      (node (ref "JP1") (pin "35") (pinfunction "35_35") (pintype "passive"))
    )
    (net (code "134") (name "unconnected-(JP1-Pad36)") (class "Default")
      (node (ref "JP1") (pin "36") (pinfunction "36_36") (pintype "passive"))
    )
    (net (code "135") (name "unconnected-(JP1-Pad37)") (class "Default")
      (node (ref "JP1") (pin "37") (pinfunction "37_37") (pintype "passive"))
    )
    (net (code "136") (name "unconnected-(JP1-Pad38)") (class "Default")
      (node (ref "JP1") (pin "38") (pinfunction "38_38") (pintype "passive"))
    )
    (net (code "137") (name "unconnected-(JP1-Pad39)") (class "Default")
      (node (ref "JP1") (pin "39") (pinfunction "39_39") (pintype "passive"))
    )
    (net (code "138") (name "unconnected-(JP1-Pad40)") (class "Default")
      (node (ref "JP1") (pin "40") (pinfunction "40_40") (pintype "passive"))
    )
    (net (code "139") (name "unconnected-(V1C-A-Pad3)") (class "Default")
      (node (ref "V1") (pin "3") (pinfunction "A_3") (pintype "input"))
    )
    (net (code "140") (name "unconnected-(V1C-B-Pad4)") (class "Default")
      (node (ref "V1") (pin "4") (pinfunction "B_4") (pintype "input"))
    )
    (net (code "141") (name "unconnected-(V1C-C-Pad5)") (class "Default")
      (node (ref "V1") (pin "5") (pinfunction "C_5") (pintype "input"))
    )
    (net (code "142") (name "unconnected-(V1C-CLK-Pad2)") (class "Default")
      (node (ref "V1") (pin "2") (pinfunction "CLK_2") (pintype "input"))
    )
    (net (code "143") (name "unconnected-(V1C-D-Pad6)") (class "Default")
      (node (ref "V1") (pin "6") (pinfunction "D_6") (pintype "input"))
    )
    (net (code "144") (name "unconnected-(V1C-ENP-Pad7)") (class "Default")
      (node (ref "V1") (pin "7") (pinfunction "ENP_7") (pintype "input"))
    )
    (net (code "145") (name "unconnected-(V1C-ENT-Pad10)") (class "Default")
      (node (ref "V1") (pin "10") (pinfunction "ENT_10") (pintype "input"))
    )
    (net (code "146") (name "unconnected-(V1C-RCO-Pad15)") (class "Default")
      (node (ref "V1") (pin "15") (pinfunction "RCO_15") (pintype "output"))
    )
    (net (code "147") (name "unconnected-(V1C-~{CLR}-Pad1)") (class "Default")
      (node (ref "V1") (pin "1") (pinfunction "~{CLR}_1") (pintype "input"))
    )
    (net (code "148") (name "unconnected-(V1C-~{LOAD}-Pad9)") (class "Default")
      (node (ref "V1") (pin "9") (pinfunction "~{LOAD}_9") (pintype "input"))
    )
  )
)
